# clare-head.net
KiCad netlist of a schematic drawn in EAGLE
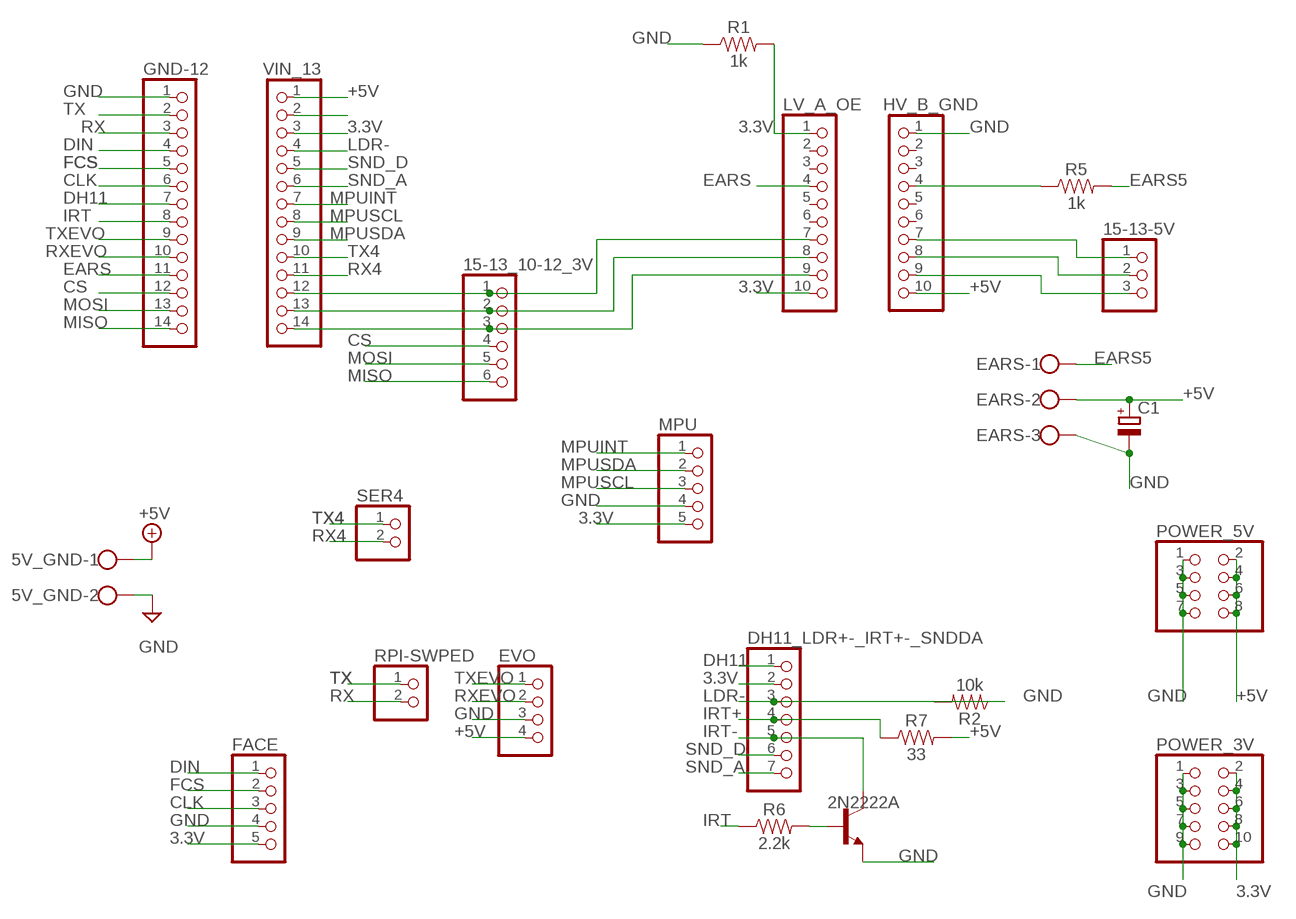
[diagram p0: schematic, sheet 1]

(export (version "E")
  (design (tool "Eeschema 10.0.6"))
  (components
    (comp (ref "2N2222A")
      (value "2N2222A-NPN-TO18-EBC")
      (footprint "eagle-import:TO18")
      (libsource (lib "eagle-import") (part "-NPN-TO18-EBC2N2222A"))
    )
    (comp (ref "5V_GND")
      (value "W237-102")
      (footprint "eagle-import:W237-102")
      (fields (field (name "MPN") "237-102"))
      (libsource (lib "eagle-import") (part "W237-102"))
    )
    (comp (ref "15-13-5V")
      (value "PINHD-1X3")
      (footprint "eagle-import:1X03")
      (libsource (lib "eagle-import") (part "PINHD-1X3"))
    )
    (comp (ref "15-13_10-12_3V")
      (value "PINHD-1X6")
      (footprint "eagle-import:1X06")
      (libsource (lib "eagle-import") (part "PINHD-1X6"))
    )
    (comp (ref "C1")
      (value "CPOL-EUE2,5-6E")
      (footprint "eagle-import:E2,5-6E")
      (libsource (lib "eagle-import") (part "CPOL-EUE2,5-6E"))
    )
    (comp (ref "DH11_LDR+-_IRT+-_SNDDA")
      (value "PINHD-1X7")
      (footprint "eagle-import:1X07")
      (libsource (lib "eagle-import") (part "PINHD-1X7"))
    )
    (comp (ref "EARS")
      (value "W237-103")
      (footprint "eagle-import:W237-103")
      (fields (field (name "MPN") "237-103"))
      (libsource (lib "eagle-import") (part "W237-103"))
    )
    (comp (ref "EVO")
      (value "PINHD-1X4")
      (footprint "eagle-import:1X04")
      (libsource (lib "eagle-import") (part "PINHD-1X4"))
    )
    (comp (ref "FACE")
      (value "PINHD-1X5")
      (footprint "eagle-import:1X05")
      (libsource (lib "eagle-import") (part "PINHD-1X5"))
    )
    (comp (ref "GND-12")
      (value "PINHD-1X14")
      (footprint "eagle-import:1X14")
      (libsource (lib "eagle-import") (part "PINHD-1X14"))
    )
    (comp (ref "HV_B_GND")
      (value "PINHD-1X10")
      (footprint "eagle-import:1X10")
      (libsource (lib "eagle-import") (part "PINHD-1X10"))
    )
    (comp (ref "LV_A_OE")
      (value "PINHD-1X10")
      (footprint "eagle-import:1X10")
      (libsource (lib "eagle-import") (part "PINHD-1X10"))
    )
    (comp (ref "MPU")
      (value "PINHD-1X5")
      (footprint "eagle-import:1X05")
      (libsource (lib "eagle-import") (part "PINHD-1X5"))
    )
    (comp (ref "POWER_3V")
      (value "PINHD-2X5")
      (footprint "eagle-import:2X05")
      (libsource (lib "eagle-import") (part "PINHD-2X5"))
    )
    (comp (ref "POWER_5V")
      (value "PINHD-2X4")
      (footprint "eagle-import:2X04")
      (libsource (lib "eagle-import") (part "PINHD-2X4"))
    )
    (comp (ref "R1")
      (value "1k")
      (footprint "eagle-import:AXIAL-0.3")
      (libsource (lib "eagle-import") (part "1KOHM-HORIZ-1/4W-1%"))
    )
    (comp (ref "R2")
      (value "10k")
      (footprint "eagle-import:AXIAL-0.3")
      (libsource (lib "eagle-import") (part "1KOHM-HORIZ-1/4W-1%"))
    )
    (comp (ref "R5")
      (value "1k")
      (footprint "eagle-import:AXIAL-0.3")
      (libsource (lib "eagle-import") (part "1KOHM-HORIZ-1/4W-1%"))
    )
    (comp (ref "R6")
      (value "2.2k")
      (footprint "eagle-import:AXIAL-0.3")
      (libsource (lib "eagle-import") (part "1KOHM-HORIZ-1/4W-1%"))
    )
    (comp (ref "R7")
      (value "33")
      (footprint "eagle-import:AXIAL-0.3")
      (libsource (lib "eagle-import") (part "1KOHM-HORIZ-1/4W-1%"))
    )
    (comp (ref "RPI-SWPED")
      (value "PINHD-1X2")
      (footprint "eagle-import:1X02")
      (libsource (lib "eagle-import") (part "PINHD-1X2"))
    )
    (comp (ref "SER4")
      (value "PINHD-1X2")
      (footprint "eagle-import:1X02")
      (libsource (lib "eagle-import") (part "PINHD-1X2"))
    )
    (comp (ref "VIN_13")
      (value "PINHD-1X14")
      (footprint "eagle-import:1X14")
      (libsource (lib "eagle-import") (part "PINHD-1X14"))
    )
  )
  (nets
    (net (code "1") (name "+5V") (class "Default")
      (node (ref "5V_GND") (pin "1") (pinfunction "KL_1") (pintype "passive"))
      (node (ref "C1") (pin "+") (pinfunction "+_+") (pintype "passive"))
      (node (ref "EARS") (pin "2") (pinfunction "KL_2") (pintype "passive"))
      (node (ref "EVO") (pin "4") (pinfunction "4_4") (pintype "passive"))
      (node (ref "HV_B_GND") (pin "10") (pinfunction "10_10") (pintype "passive"))
      (node (ref "POWER_5V") (pin "2") (pinfunction "2_2") (pintype "passive"))
      (node (ref "POWER_5V") (pin "4") (pinfunction "4_4") (pintype "passive"))
      (node (ref "POWER_5V") (pin "6") (pinfunction "6_6") (pintype "passive"))
      (node (ref "POWER_5V") (pin "8") (pinfunction "8_8") (pintype "passive"))
      (node (ref "R7") (pin "P$2") (pinfunction "2_P$2") (pintype "passive"))
      (node (ref "VIN_13") (pin "1") (pinfunction "1_1") (pintype "passive"))
    )
    (net (code "2") (name "/3.3V") (class "Default")
      (node (ref "DH11_LDR+-_IRT+-_SNDDA") (pin "2") (pinfunction "2_2") (pintype "passive"))
      (node (ref "FACE") (pin "5") (pinfunction "5_5") (pintype "passive"))
      (node (ref "LV_A_OE") (pin "1") (pinfunction "1_1") (pintype "passive"))
      (node (ref "LV_A_OE") (pin "10") (pinfunction "10_10") (pintype "passive"))
      (node (ref "MPU") (pin "5") (pinfunction "5_5") (pintype "passive"))
      (node (ref "POWER_3V") (pin "10") (pinfunction "10_10") (pintype "passive"))
      (node (ref "POWER_3V") (pin "2") (pinfunction "2_2") (pintype "passive"))
      (node (ref "POWER_3V") (pin "4") (pinfunction "4_4") (pintype "passive"))
      (node (ref "POWER_3V") (pin "6") (pinfunction "6_6") (pintype "passive"))
      (node (ref "POWER_3V") (pin "8") (pinfunction "8_8") (pintype "passive"))
      (node (ref "R1") (pin "P$2") (pinfunction "2_P$2") (pintype "passive"))
      (node (ref "VIN_13") (pin "3") (pinfunction "3_3") (pintype "passive"))
    )
    (net (code "3") (name "/CLK") (class "Default")
      (node (ref "FACE") (pin "3") (pinfunction "3_3") (pintype "passive"))
      (node (ref "GND-12") (pin "6") (pinfunction "6_6") (pintype "passive"))
    )
    (net (code "4") (name "/CS") (class "Default")
      (node (ref "15-13_10-12_3V") (pin "4") (pinfunction "4_4") (pintype "passive"))
      (node (ref "GND-12") (pin "12") (pinfunction "12_12") (pintype "passive"))
    )
    (net (code "5") (name "/DH11") (class "Default")
      (node (ref "DH11_LDR+-_IRT+-_SNDDA") (pin "1") (pinfunction "1_1") (pintype "passive"))
      (node (ref "GND-12") (pin "7") (pinfunction "7_7") (pintype "passive"))
    )
    (net (code "6") (name "/DIN") (class "Default")
      (node (ref "FACE") (pin "1") (pinfunction "1_1") (pintype "passive"))
      (node (ref "GND-12") (pin "4") (pinfunction "4_4") (pintype "passive"))
    )
    (net (code "7") (name "/EARS") (class "Default")
      (node (ref "GND-12") (pin "11") (pinfunction "11_11") (pintype "passive"))
      (node (ref "LV_A_OE") (pin "4") (pinfunction "4_4") (pintype "passive"))
    )
    (net (code "8") (name "/EARS5") (class "Default")
      (node (ref "EARS") (pin "1") (pinfunction "KL_1") (pintype "passive"))
      (node (ref "R5") (pin "P$2") (pinfunction "2_P$2") (pintype "passive"))
    )
    (net (code "9") (name "/FCS") (class "Default")
      (node (ref "FACE") (pin "2") (pinfunction "2_2") (pintype "passive"))
      (node (ref "GND-12") (pin "5") (pinfunction "5_5") (pintype "passive"))
    )
    (net (code "10") (name "/IRT") (class "Default")
      (node (ref "GND-12") (pin "8") (pinfunction "8_8") (pintype "passive"))
      (node (ref "R6") (pin "P$1") (pinfunction "1_P$1") (pintype "passive"))
    )
    (net (code "11") (name "/IRT+") (class "Default")
      (node (ref "DH11_LDR+-_IRT+-_SNDDA") (pin "4") (pinfunction "4_4") (pintype "passive"))
      (node (ref "R7") (pin "P$1") (pinfunction "1_P$1") (pintype "passive"))
    )
    (net (code "12") (name "/IRT-") (class "Default")
      (node (ref "2N2222A") (pin "3") (pinfunction "C_3") (pintype "passive"))
      (node (ref "DH11_LDR+-_IRT+-_SNDDA") (pin "5") (pinfunction "5_5") (pintype "passive"))
    )
    (net (code "13") (name "/LDR-") (class "Default")
      (node (ref "DH11_LDR+-_IRT+-_SNDDA") (pin "3") (pinfunction "3_3") (pintype "passive"))
      (node (ref "R2") (pin "P$2") (pinfunction "2_P$2") (pintype "passive"))
      (node (ref "VIN_13") (pin "4") (pinfunction "4_4") (pintype "passive"))
    )
    (net (code "14") (name "/MISO") (class "Default")
      (node (ref "15-13_10-12_3V") (pin "6") (pinfunction "6_6") (pintype "passive"))
      (node (ref "GND-12") (pin "14") (pinfunction "14_14") (pintype "passive"))
    )
    (net (code "15") (name "/MOSI") (class "Default")
      (node (ref "15-13_10-12_3V") (pin "5") (pinfunction "5_5") (pintype "passive"))
      (node (ref "GND-12") (pin "13") (pinfunction "13_13") (pintype "passive"))
    )
    (net (code "16") (name "/MPUINT") (class "Default")
      (node (ref "MPU") (pin "1") (pinfunction "1_1") (pintype "passive"))
      (node (ref "VIN_13") (pin "7") (pinfunction "7_7") (pintype "passive"))
    )
    (net (code "17") (name "/MPUSCL") (class "Default")
      (node (ref "MPU") (pin "3") (pinfunction "3_3") (pintype "passive"))
      (node (ref "VIN_13") (pin "8") (pinfunction "8_8") (pintype "passive"))
    )
    (net (code "18") (name "/MPUSDA") (class "Default")
      (node (ref "MPU") (pin "2") (pinfunction "2_2") (pintype "passive"))
      (node (ref "VIN_13") (pin "9") (pinfunction "9_9") (pintype "passive"))
    )
    (net (code "19") (name "/RX") (class "Default")
      (node (ref "GND-12") (pin "3") (pinfunction "3_3") (pintype "passive"))
      (node (ref "RPI-SWPED") (pin "2") (pinfunction "2_2") (pintype "passive"))
    )
    (net (code "20") (name "/RX4") (class "Default")
      (node (ref "SER4") (pin "2") (pinfunction "2_2") (pintype "passive"))
      (node (ref "VIN_13") (pin "11") (pinfunction "11_11") (pintype "passive"))
    )
    (net (code "21") (name "/RXEVO") (class "Default")
      (node (ref "EVO") (pin "2") (pinfunction "2_2") (pintype "passive"))
      (node (ref "GND-12") (pin "10") (pinfunction "10_10") (pintype "passive"))
    )
    (net (code "22") (name "/SND_A") (class "Default")
      (node (ref "DH11_LDR+-_IRT+-_SNDDA") (pin "7") (pinfunction "7_7") (pintype "passive"))
      (node (ref "VIN_13") (pin "6") (pinfunction "6_6") (pintype "passive"))
    )
    (net (code "23") (name "/SND_D") (class "Default")
      (node (ref "DH11_LDR+-_IRT+-_SNDDA") (pin "6") (pinfunction "6_6") (pintype "passive"))
      (node (ref "VIN_13") (pin "5") (pinfunction "5_5") (pintype "passive"))
    )
    (net (code "24") (name "/TX") (class "Default")
      (node (ref "GND-12") (pin "2") (pinfunction "2_2") (pintype "passive"))
      (node (ref "RPI-SWPED") (pin "1") (pinfunction "1_1") (pintype "passive"))
    )
    (net (code "25") (name "/TX4") (class "Default")
      (node (ref "SER4") (pin "1") (pinfunction "1_1") (pintype "passive"))
      (node (ref "VIN_13") (pin "10") (pinfunction "10_10") (pintype "passive"))
    )
    (net (code "26") (name "/TXEVO") (class "Default")
      (node (ref "EVO") (pin "1") (pinfunction "1_1") (pintype "passive"))
      (node (ref "GND-12") (pin "9") (pinfunction "9_9") (pintype "passive"))
    )
    (net (code "27") (name "GND") (class "Default")
      (node (ref "2N2222A") (pin "1") (pinfunction "E_1") (pintype "passive"))
      (node (ref "5V_GND") (pin "2") (pinfunction "KL_2") (pintype "passive"))
      (node (ref "C1") (pin "-") (pinfunction "-_-") (pintype "passive"))
      (node (ref "EARS") (pin "3") (pinfunction "KL_3") (pintype "passive"))
      (node (ref "EVO") (pin "3") (pinfunction "3_3") (pintype "passive"))
      (node (ref "FACE") (pin "4") (pinfunction "4_4") (pintype "passive"))
      (node (ref "GND-12") (pin "1") (pinfunction "1_1") (pintype "passive"))
      (node (ref "HV_B_GND") (pin "1") (pinfunction "1_1") (pintype "passive"))
      (node (ref "MPU") (pin "4") (pinfunction "4_4") (pintype "passive"))
      (node (ref "POWER_3V") (pin "1") (pinfunction "1_1") (pintype "passive"))
      (node (ref "POWER_3V") (pin "3") (pinfunction "3_3") (pintype "passive"))
      (node (ref "POWER_3V") (pin "5") (pinfunction "5_5") (pintype "passive"))
      (node (ref "POWER_3V") (pin "7") (pinfunction "7_7") (pintype "passive"))
      (node (ref "POWER_3V") (pin "9") (pinfunction "9_9") (pintype "passive"))
      (node (ref "POWER_5V") (pin "1") (pinfunction "1_1") (pintype "passive"))
      (node (ref "POWER_5V") (pin "3") (pinfunction "3_3") (pintype "passive"))
      (node (ref "POWER_5V") (pin "5") (pinfunction "5_5") (pintype "passive"))
      (node (ref "POWER_5V") (pin "7") (pinfunction "7_7") (pintype "passive"))
      (node (ref "R1") (pin "P$1") (pinfunction "1_P$1") (pintype "passive"))
      (node (ref "R2") (pin "P$1") (pinfunction "1_P$1") (pintype "passive"))
    )
    (net (code "28") (name "Net-(2N2222A-B)") (class "Default")
      (node (ref "2N2222A") (pin "2") (pinfunction "B_2") (pintype "passive"))
      (node (ref "R6") (pin "P$2") (pinfunction "2_P$2") (pintype "passive"))
    )
    (net (code "29") (name "Net-(15-13-5V-Pad1)") (class "Default")
      (node (ref "15-13-5V") (pin "1") (pinfunction "1_1") (pintype "passive"))
      (node (ref "HV_B_GND") (pin "7") (pinfunction "7_7") (pintype "passive"))
    )
    (net (code "30") (name "Net-(15-13-5V-Pad2)") (class "Default")
      (node (ref "15-13-5V") (pin "2") (pinfunction "2_2") (pintype "passive"))
      (node (ref "HV_B_GND") (pin "8") (pinfunction "8_8") (pintype "passive"))
    )
    (net (code "31") (name "Net-(15-13-5V-Pad3)") (class "Default")
      (node (ref "15-13-5V") (pin "3") (pinfunction "3_3") (pintype "passive"))
      (node (ref "HV_B_GND") (pin "9") (pinfunction "9_9") (pintype "passive"))
    )
    (net (code "32") (name "Net-(15-13_10-12_3V-Pad1)") (class "Default")
      (node (ref "15-13_10-12_3V") (pin "1") (pinfunction "1_1") (pintype "passive"))
      (node (ref "LV_A_OE") (pin "7") (pinfunction "7_7") (pintype "passive"))
      (node (ref "VIN_13") (pin "12") (pinfunction "12_12") (pintype "passive"))
    )
    (net (code "33") (name "Net-(15-13_10-12_3V-Pad2)") (class "Default")
      (node (ref "15-13_10-12_3V") (pin "2") (pinfunction "2_2") (pintype "passive"))
      (node (ref "LV_A_OE") (pin "8") (pinfunction "8_8") (pintype "passive"))
      (node (ref "VIN_13") (pin "13") (pinfunction "13_13") (pintype "passive"))
    )
    (net (code "34") (name "Net-(15-13_10-12_3V-Pad3)") (class "Default")
      (node (ref "15-13_10-12_3V") (pin "3") (pinfunction "3_3") (pintype "passive"))
      (node (ref "LV_A_OE") (pin "9") (pinfunction "9_9") (pintype "passive"))
      (node (ref "VIN_13") (pin "14") (pinfunction "14_14") (pintype "passive"))
    )
    (net (code "35") (name "Net-(R5-1)") (class "Default")
      (node (ref "HV_B_GND") (pin "4") (pinfunction "4_4") (pintype "passive"))
      (node (ref "R5") (pin "P$1") (pinfunction "1_P$1") (pintype "passive"))
    )
    (net (code "36") (name "unconnected-(HV_B_GND-Pad2)") (class "Default")
      (node (ref "HV_B_GND") (pin "2") (pinfunction "2_2") (pintype "passive"))
    )
    (net (code "37") (name "unconnected-(HV_B_GND-Pad3)") (class "Default")
      (node (ref "HV_B_GND") (pin "3") (pinfunction "3_3") (pintype "passive"))
    )
    (net (code "38") (name "unconnected-(HV_B_GND-Pad5)") (class "Default")
      (node (ref "HV_B_GND") (pin "5") (pinfunction "5_5") (pintype "passive"))
    )
    (net (code "39") (name "unconnected-(HV_B_GND-Pad6)") (class "Default")
      (node (ref "HV_B_GND") (pin "6") (pinfunction "6_6") (pintype "passive"))
    )
    (net (code "40") (name "unconnected-(LV_A_OE-Pad2)") (class "Default")
      (node (ref "LV_A_OE") (pin "2") (pinfunction "2_2") (pintype "passive"))
    )
    (net (code "41") (name "unconnected-(LV_A_OE-Pad3)") (class "Default")
      (node (ref "LV_A_OE") (pin "3") (pinfunction "3_3") (pintype "passive"))
    )
    (net (code "42") (name "unconnected-(LV_A_OE-Pad5)") (class "Default")
      (node (ref "LV_A_OE") (pin "5") (pinfunction "5_5") (pintype "passive"))
    )
    (net (code "43") (name "unconnected-(LV_A_OE-Pad6)") (class "Default")
      (node (ref "LV_A_OE") (pin "6") (pinfunction "6_6") (pintype "passive"))
    )
    (net (code "44") (name "unconnected-(VIN_13-Pad2)") (class "Default")
      (node (ref "VIN_13") (pin "2") (pinfunction "2_2") (pintype "passive"))
    )
  )
)
